# RS232_2xNPN.net
KiCad netlist of a schematic drawn in EAGLE
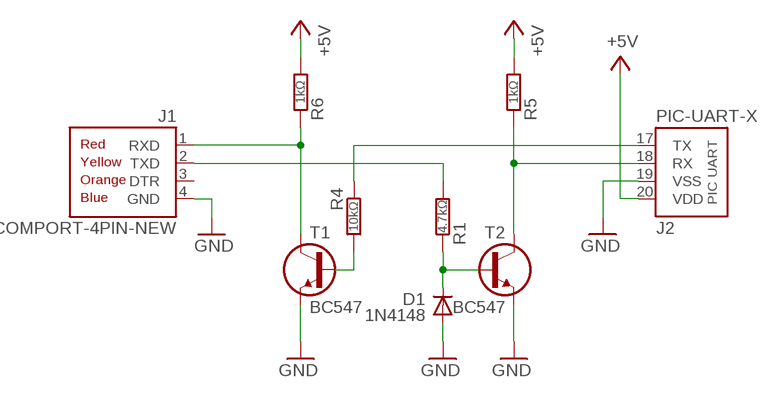
[diagram p0: schematic, sheet 1]

(export (version "E")
  (design (tool "Eeschema 10.0.6"))
  (components
    (comp (ref "D1")
      (value "1N4148")
      (footprint "eagle-import:DO34-7")
      (libsource (lib "eagle-import") (part "1N414834-7"))
    )
    (comp (ref "J1")
      (value "COMPORT-4PIN-NEW")
      (footprint "eagle-import:RS232-4PIN-NEW")
      (libsource (lib "eagle-import") (part "COMPORT-4PIN-NEW"))
    )
    (comp (ref "J2")
      (value "PIC-UART-X")
      (footprint "eagle-import:PIC-UART-X")
      (libsource (lib "eagle-import") (part "PIC-UART-X"))
    )
    (comp (ref "R1")
      (value "4.7kΩ")
      (footprint "eagle-import:0202_7")
      (libsource (lib "eagle-import") (part "R0202/7"))
    )
    (comp (ref "R4")
      (value "10kΩ")
      (footprint "eagle-import:0202_7-V")
      (libsource (lib "eagle-import") (part "R0202/7-V"))
    )
    (comp (ref "R5")
      (value "1kΩ")
      (footprint "eagle-import:0202_7-V")
      (libsource (lib "eagle-import") (part "R0202/7-V"))
    )
    (comp (ref "R6")
      (value "1kΩ")
      (footprint "eagle-import:0202_7")
      (libsource (lib "eagle-import") (part "R0202/7"))
    )
    (comp (ref "T1")
      (value "BC547")
      (footprint "eagle-import:TO92-CBE")
      (libsource (lib "eagle-import") (part "BC547CBE"))
    )
    (comp (ref "T2")
      (value "BC547")
      (footprint "eagle-import:TO92-CBE")
      (libsource (lib "eagle-import") (part "BC547CBE"))
    )
  )
  (nets
    (net (code "1") (name "+5V") (class "Default")
      (node (ref "J2") (pin "20") (pinfunction "VDD_20") (pintype "passive"))
      (node (ref "R5") (pin "2") (pinfunction "2_2") (pintype "passive"))
      (node (ref "R6") (pin "2") (pinfunction "2_2") (pintype "passive"))
    )
    (net (code "2") (name "GND") (class "Default")
      (node (ref "D1") (pin "A") (pinfunction "A_A") (pintype "passive"))
      (node (ref "J1") (pin "4") (pinfunction "GND_4") (pintype "passive"))
      (node (ref "J2") (pin "19") (pinfunction "VSS_19") (pintype "passive"))
      (node (ref "T1") (pin "E") (pinfunction "E_E") (pintype "passive"))
      (node (ref "T2") (pin "E") (pinfunction "E_E") (pintype "passive"))
    )
    (net (code "3") (name "Net-(D1-PadC)") (class "Default")
      (node (ref "D1") (pin "C") (pinfunction "C_C") (pintype "passive"))
      (node (ref "R1") (pin "1") (pinfunction "1_1") (pintype "passive"))
      (node (ref "T2") (pin "B") (pinfunction "B_B") (pintype "passive"))
    )
    (net (code "4") (name "Net-(J1-RXD)") (class "Default")
      (node (ref "J1") (pin "1") (pinfunction "RXD_1") (pintype "passive"))
      (node (ref "R6") (pin "1") (pinfunction "1_1") (pintype "passive"))
      (node (ref "T1") (pin "C") (pinfunction "C_C") (pintype "passive"))
    )
    (net (code "5") (name "Net-(J1-TXD)") (class "Default")
      (node (ref "J1") (pin "2") (pinfunction "TXD_2") (pintype "passive"))
      (node (ref "R1") (pin "2") (pinfunction "2_2") (pintype "passive"))
    )
    (net (code "6") (name "Net-(J2-RX)") (class "Default")
      (node (ref "J2") (pin "18") (pinfunction "RX_18") (pintype "passive"))
      (node (ref "R5") (pin "1") (pinfunction "1_1") (pintype "passive"))
      (node (ref "T2") (pin "C") (pinfunction "C_C") (pintype "passive"))
    )
    (net (code "7") (name "Net-(J2-TX)") (class "Default")
      (node (ref "J2") (pin "17") (pinfunction "TX_17") (pintype "passive"))
      (node (ref "R4") (pin "1") (pinfunction "1_1") (pintype "passive"))
    )
    (net (code "8") (name "Net-(R4-Pad2)") (class "Default")
      (node (ref "R4") (pin "2") (pinfunction "2_2") (pintype "passive"))
      (node (ref "T1") (pin "B") (pinfunction "B_B") (pintype "passive"))
    )
    (net (code "9") (name "unconnected-(J1-DTR-Pad3)") (class "Default")
      (node (ref "J1") (pin "3") (pinfunction "DTR_3") (pintype "passive"))
    )
  )
)
